# main.net
KiCad netlist of a schematic drawn in EAGLE
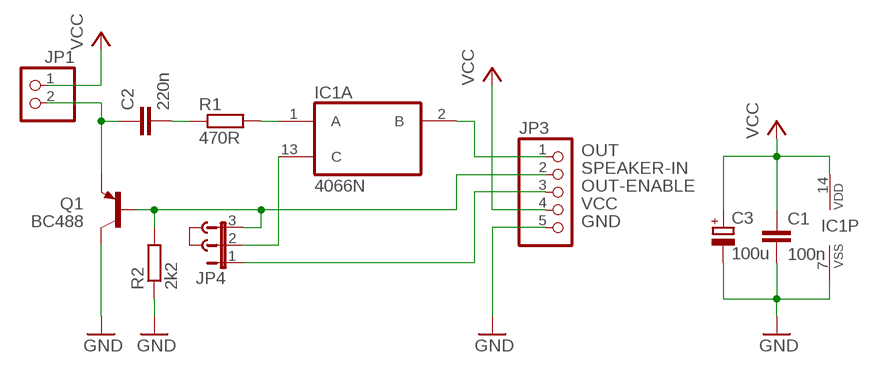
[diagram p0: schematic, sheet 1]

(export (version "E")
  (design (tool "Eeschema 10.0.6"))
  (components
    (comp (ref "C1")
      (value "100n")
      (footprint "eagle-import:C1206")
      (libsource (lib "eagle-import") (part "C-EUC1206"))
    )
    (comp (ref "C2")
      (value "220n")
      (footprint "eagle-import:C025-025X050")
      (libsource (lib "eagle-import") (part "C-EU025-025X050"))
    )
    (comp (ref "C3")
      (value "100u")
      (footprint "eagle-import:E2-5")
      (libsource (lib "eagle-import") (part "CPOL-EUE2-5"))
    )
    (comp (ref "IC1")
      (value "4066N")
      (footprint "eagle-import:DIL14")
      (libsource (lib "eagle-import") (part "4066N"))
    )
    (comp (ref "J1")
      (value "JUMPER")
      (footprint "eagle-import:JUMP")
      (libsource (lib "eagle-import") (part "JUMPER"))
    )
    (comp (ref "JP1")
      (value "PINHD-1X2")
      (footprint "eagle-import:1X02")
      (libsource (lib "eagle-import") (part "PINHD-1X2"))
    )
    (comp (ref "JP3")
      (value "PINHD-1X5")
      (footprint "eagle-import:1X05")
      (libsource (lib "eagle-import") (part "PINHD-1X5"))
    )
    (comp (ref "JP4")
      (value "JP2E")
      (footprint "eagle-import:JP2")
      (libsource (lib "eagle-import") (part "JP2E"))
    )
    (comp (ref "Q1")
      (value "BC488")
      (footprint "eagle-import:TO92-EBC")
      (libsource (lib "eagle-import") (part "BC488"))
    )
    (comp (ref "R1")
      (value "470R")
      (footprint "eagle-import:0204_7")
      (libsource (lib "eagle-import") (part "R-EU_0204/7"))
    )
    (comp (ref "R2")
      (value "2k2")
      (footprint "eagle-import:R1206")
      (libsource (lib "eagle-import") (part "R-EU_R1206"))
    )
  )
  (nets
    (net (code "1") (name "/OUT") (class "Default")
      (node (ref "IC1") (pin "2") (pinfunction "B_2") (pintype "tri_state"))
      (node (ref "JP3") (pin "1") (pinfunction "1_1") (pintype "passive"))
    )
    (net (code "2") (name "/OUT-ENABLE") (class "Default")
      (node (ref "JP3") (pin "3") (pinfunction "3_3") (pintype "passive"))
      (node (ref "JP4") (pin "1") (pinfunction "1_1") (pintype "passive"))
    )
    (net (code "3") (name "/SPEAKER-IN") (class "Default")
      (node (ref "JP3") (pin "2") (pinfunction "2_2") (pintype "passive"))
      (node (ref "JP4") (pin "3") (pinfunction "3_3") (pintype "passive"))
      (node (ref "Q1") (pin "B") (pinfunction "B_B") (pintype "passive"))
      (node (ref "R2") (pin "2") (pinfunction "2_2") (pintype "passive"))
    )
    (net (code "4") (name "GND") (class "Default")
      (node (ref "C1") (pin "2") (pinfunction "2_2") (pintype "passive"))
      (node (ref "C3") (pin "-") (pinfunction "-_-") (pintype "passive"))
      (node (ref "IC1") (pin "7") (pinfunction "VSS_7") (pintype "power_in"))
      (node (ref "JP3") (pin "5") (pinfunction "5_5") (pintype "passive"))
      (node (ref "Q1") (pin "C") (pinfunction "C_C") (pintype "passive"))
      (node (ref "R2") (pin "1") (pinfunction "1_1") (pintype "passive"))
    )
    (net (code "5") (name "Net-(C2-Pad1)") (class "Default")
      (node (ref "C2") (pin "1") (pinfunction "1_1") (pintype "passive"))
      (node (ref "JP1") (pin "2") (pinfunction "2_2") (pintype "passive"))
      (node (ref "Q1") (pin "E") (pinfunction "E_E") (pintype "passive"))
    )
    (net (code "6") (name "Net-(C2-Pad2)") (class "Default")
      (node (ref "C2") (pin "2") (pinfunction "2_2") (pintype "passive"))
      (node (ref "R1") (pin "1") (pinfunction "1_1") (pintype "passive"))
    )
    (net (code "7") (name "Net-(IC1A-A)") (class "Default")
      (node (ref "IC1") (pin "1") (pinfunction "A_1") (pintype "tri_state"))
      (node (ref "R1") (pin "2") (pinfunction "2_2") (pintype "passive"))
    )
    (net (code "8") (name "Net-(IC1A-C)") (class "Default")
      (node (ref "IC1") (pin "13") (pinfunction "C_13") (pintype "input"))
      (node (ref "JP4") (pin "2") (pinfunction "2_2") (pintype "passive"))
    )
    (net (code "9") (name "VCC") (class "Default")
      (node (ref "C1") (pin "1") (pinfunction "1_1") (pintype "passive"))
      (node (ref "C3") (pin "+") (pinfunction "+_+") (pintype "passive"))
      (node (ref "IC1") (pin "14") (pinfunction "VDD_14") (pintype "power_in"))
      (node (ref "JP1") (pin "1") (pinfunction "1_1") (pintype "passive"))
      (node (ref "JP3") (pin "4") (pinfunction "4_4") (pintype "passive"))
    )
  )
)
